# io.net
KiCad netlist of a schematic drawn in Altium Designer
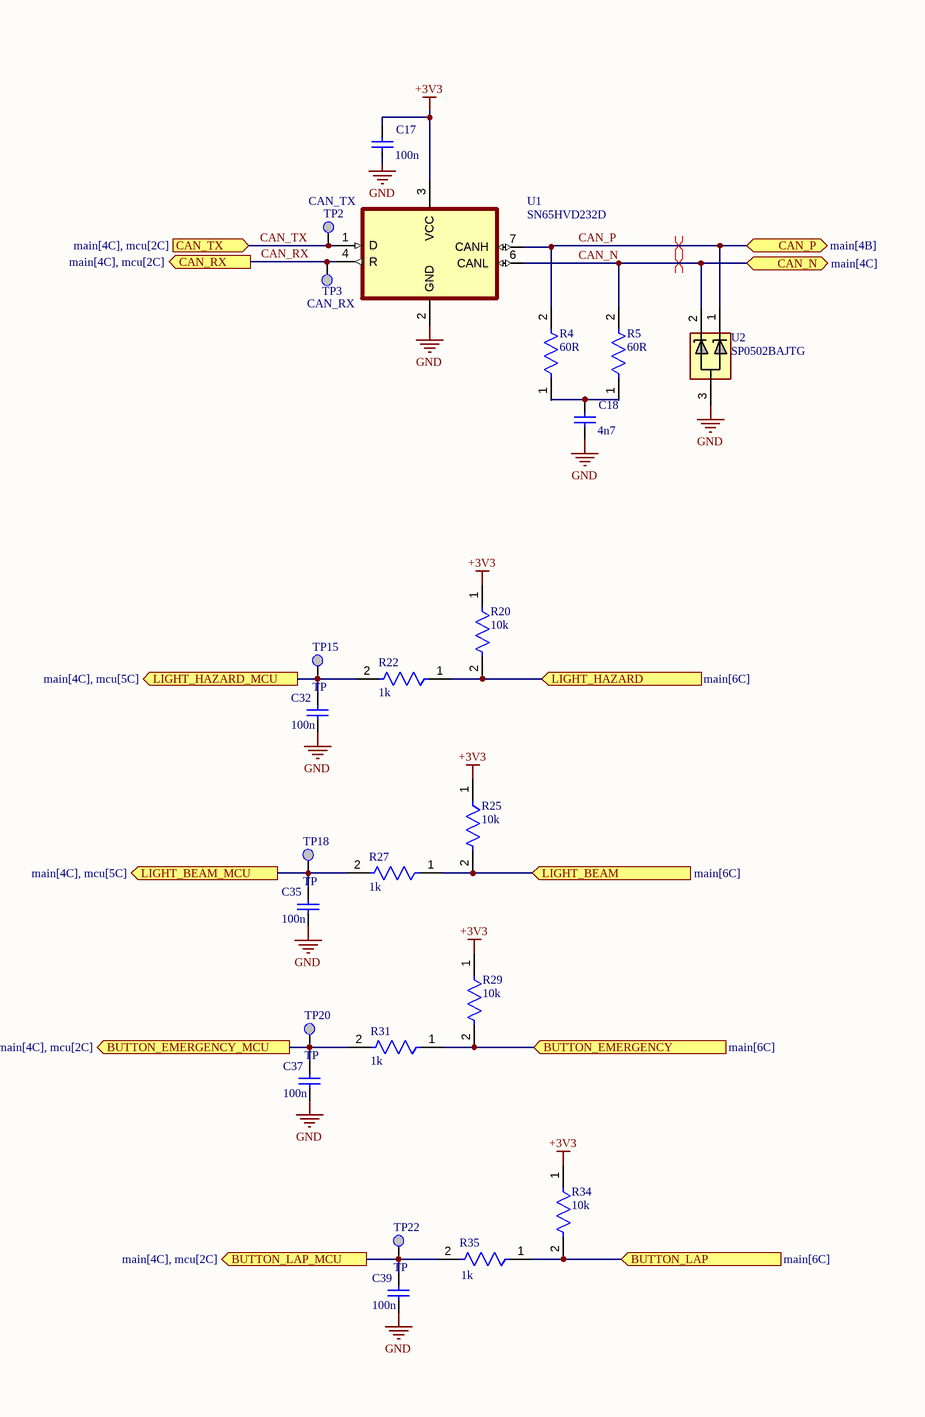
[diagram p0: io.SchDoc, left]
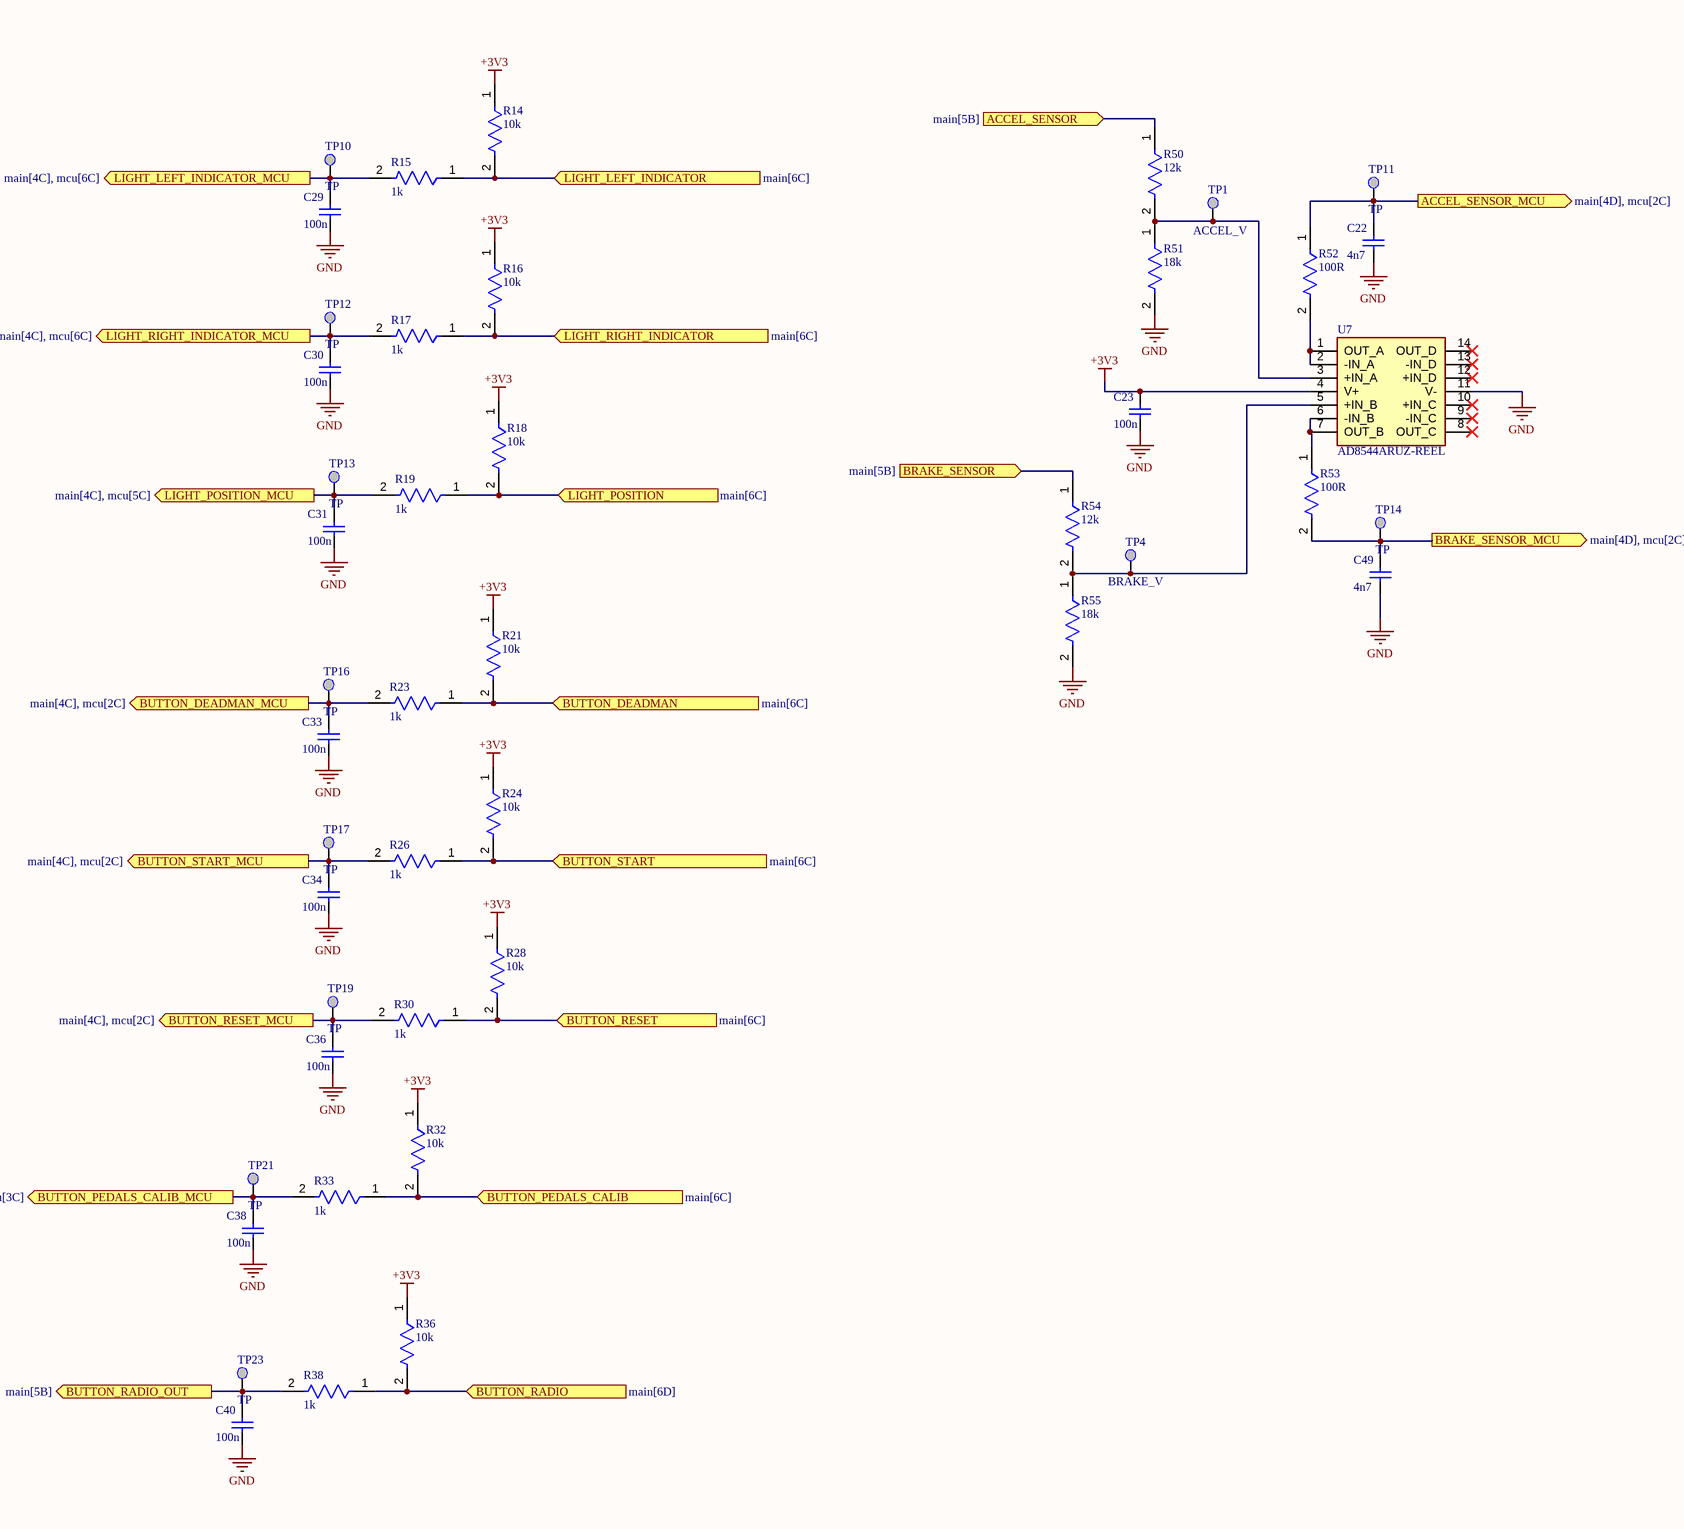
[diagram p1: io.SchDoc, right]

(export (version "E")
  (design (tool "Eeschema 10.0.6"))
  (components
    (comp (ref "C17")
      (value "100n")
      (footprint "CAPC1206(3216)150_L")
      (description "CAP 1.8uF 10V ±5% 1206 (3216 Metric) Thickness 1.45mm SMD")
      (fields (field (name "TOLERANCE") "Â±5%"))
      (libsource (lib "Altium Content Vault") (part "CAP"))
    )
    (comp (ref "C18")
      (value "4n7")
      (footprint "CAPC1206(3216)150_L")
      (description "CAP 1.8uF 10V ±5% 1206 (3216 Metric) Thickness 1.45mm SMD")
      (fields (field (name "TOLERANCE") "Â±5%"))
      (libsource (lib "Altium Content Vault") (part "CAP"))
    )
    (comp (ref "C22")
      (value "4n7")
      (footprint "CAPC1206(3216)150_L")
      (description "CAP 1.8uF 10V ±5% 1206 (3216 Metric) Thickness 1.45mm SMD")
      (fields (field (name "TOLERANCE") "Â±5%"))
      (libsource (lib "Altium Content Vault") (part "CAP"))
    )
    (comp (ref "C23")
      (value "100n")
      (footprint "CAPC1206(3216)150_L")
      (description "CAP 1.8uF 10V ±5% 1206 (3216 Metric) Thickness 1.45mm SMD")
      (fields (field (name "TOLERANCE") "Â±5%"))
      (libsource (lib "Altium Content Vault") (part "CAP"))
    )
    (comp (ref "C29")
      (value "100n")
      (footprint "CAPC1206(3216)150_L")
      (description "CAP 1.8uF 10V ±5% 1206 (3216 Metric) Thickness 1.45mm SMD")
      (fields (field (name "TOLERANCE") "Â±5%"))
      (libsource (lib "Altium Content Vault") (part "CAP"))
    )
    (comp (ref "C30")
      (value "100n")
      (footprint "CAPC1206(3216)150_L")
      (description "CAP 1.8uF 10V ±5% 1206 (3216 Metric) Thickness 1.45mm SMD")
      (fields (field (name "TOLERANCE") "Â±5%"))
      (libsource (lib "Altium Content Vault") (part "CAP"))
    )
    (comp (ref "C31")
      (value "100n")
      (footprint "CAPC1206(3216)150_L")
      (description "CAP 1.8uF 10V ±5% 1206 (3216 Metric) Thickness 1.45mm SMD")
      (fields (field (name "TOLERANCE") "Â±5%"))
      (libsource (lib "Altium Content Vault") (part "CAP"))
    )
    (comp (ref "C32")
      (value "100n")
      (footprint "CAPC1206(3216)150_L")
      (description "CAP 1.8uF 10V ±5% 1206 (3216 Metric) Thickness 1.45mm SMD")
      (fields (field (name "TOLERANCE") "Â±5%"))
      (libsource (lib "Altium Content Vault") (part "CAP"))
    )
    (comp (ref "C33")
      (value "100n")
      (footprint "CAPC1206(3216)150_L")
      (description "CAP 1.8uF 10V ±5% 1206 (3216 Metric) Thickness 1.45mm SMD")
      (fields (field (name "TOLERANCE") "Â±5%"))
      (libsource (lib "Altium Content Vault") (part "CAP"))
    )
    (comp (ref "C34")
      (value "100n")
      (footprint "CAPC1206(3216)150_L")
      (description "CAP 1.8uF 10V ±5% 1206 (3216 Metric) Thickness 1.45mm SMD")
      (fields (field (name "TOLERANCE") "Â±5%"))
      (libsource (lib "Altium Content Vault") (part "CAP"))
    )
    (comp (ref "C35")
      (value "100n")
      (footprint "CAPC1206(3216)150_L")
      (description "CAP 1.8uF 10V ±5% 1206 (3216 Metric) Thickness 1.45mm SMD")
      (fields (field (name "TOLERANCE") "Â±5%"))
      (libsource (lib "Altium Content Vault") (part "CAP"))
    )
    (comp (ref "C36")
      (value "100n")
      (footprint "CAPC1206(3216)150_L")
      (description "CAP 1.8uF 10V ±5% 1206 (3216 Metric) Thickness 1.45mm SMD")
      (fields (field (name "TOLERANCE") "Â±5%"))
      (libsource (lib "Altium Content Vault") (part "CAP"))
    )
    (comp (ref "C37")
      (value "100n")
      (footprint "CAPC1206(3216)150_L")
      (description "CAP 1.8uF 10V ±5% 1206 (3216 Metric) Thickness 1.45mm SMD")
      (fields (field (name "TOLERANCE") "Â±5%"))
      (libsource (lib "Altium Content Vault") (part "CAP"))
    )
    (comp (ref "C38")
      (value "100n")
      (footprint "CAPC1206(3216)150_L")
      (description "CAP 1.8uF 10V ±5% 1206 (3216 Metric) Thickness 1.45mm SMD")
      (fields (field (name "TOLERANCE") "Â±5%"))
      (libsource (lib "Altium Content Vault") (part "CAP"))
    )
    (comp (ref "C39")
      (value "100n")
      (footprint "CAPC1206(3216)150_L")
      (description "CAP 1.8uF 10V ±5% 1206 (3216 Metric) Thickness 1.45mm SMD")
      (fields (field (name "TOLERANCE") "Â±5%"))
      (libsource (lib "Altium Content Vault") (part "CAP"))
    )
    (comp (ref "C40")
      (value "100n")
      (footprint "CAPC1206(3216)150_L")
      (description "CAP 1.8uF 10V ±5% 1206 (3216 Metric) Thickness 1.45mm SMD")
      (fields (field (name "TOLERANCE") "Â±5%"))
      (libsource (lib "Altium Content Vault") (part "CAP"))
    )
    (comp (ref "C49")
      (value "4n7")
      (footprint "CAPC1206(3216)150_L")
      (description "CAP 1.8uF 10V ±5% 1206 (3216 Metric) Thickness 1.45mm SMD")
      (fields (field (name "TOLERANCE") "Â±5%"))
      (libsource (lib "Altium Content Vault") (part "CAP"))
    )
    (comp (ref "R4")
      (value "60R")
      (footprint "FP-RK73H2B-MFG")
      (description "40.2kΩ ±1% 0.25W Chip Resistor 1206 Thick Film AEC-Q200 Qualified")
      (fields (field (name "TOLERANCE") "1%"))
      (libsource (lib "Altium Content Vault") (part "1029c3af85768c4190bb7ad29bc67b5"))
    )
    (comp (ref "R5")
      (value "60R")
      (footprint "FP-RK73H2B-MFG")
      (description "40.2kΩ ±1% 0.25W Chip Resistor 1206 Thick Film AEC-Q200 Qualified")
      (fields (field (name "TOLERANCE") "1%"))
      (libsource (lib "Altium Content Vault") (part "1029c3af85768c4190bb7ad29bc67b5"))
    )
    (comp (ref "R14")
      (value "10k")
      (footprint "FP-RK73H2B-MFG")
      (description "40.2kΩ ±1% 0.25W Chip Resistor 1206 Thick Film AEC-Q200 Qualified")
      (fields (field (name "TOLERANCE") "1%"))
      (libsource (lib "Altium Content Vault") (part "1029c3af85768c4190bb7ad29bc67b5"))
    )
    (comp (ref "R15")
      (value "1k")
      (footprint "FP-RK73H2B-MFG")
      (description "40.2kΩ ±1% 0.25W Chip Resistor 1206 Thick Film AEC-Q200 Qualified")
      (fields (field (name "TOLERANCE") "1%"))
      (libsource (lib "Altium Content Vault") (part "1029c3af85768c4190bb7ad29bc67b5"))
    )
    (comp (ref "R16")
      (value "10k")
      (footprint "FP-RK73H2B-MFG")
      (description "40.2kΩ ±1% 0.25W Chip Resistor 1206 Thick Film AEC-Q200 Qualified")
      (fields (field (name "TOLERANCE") "1%"))
      (libsource (lib "Altium Content Vault") (part "1029c3af85768c4190bb7ad29bc67b5"))
    )
    (comp (ref "R17")
      (value "1k")
      (footprint "FP-RK73H2B-MFG")
      (description "40.2kΩ ±1% 0.25W Chip Resistor 1206 Thick Film AEC-Q200 Qualified")
      (fields (field (name "TOLERANCE") "1%"))
      (libsource (lib "Altium Content Vault") (part "1029c3af85768c4190bb7ad29bc67b5"))
    )
    (comp (ref "R18")
      (value "10k")
      (footprint "FP-RK73H2B-MFG")
      (description "40.2kΩ ±1% 0.25W Chip Resistor 1206 Thick Film AEC-Q200 Qualified")
      (fields (field (name "TOLERANCE") "1%"))
      (libsource (lib "Altium Content Vault") (part "1029c3af85768c4190bb7ad29bc67b5"))
    )
    (comp (ref "R19")
      (value "1k")
      (footprint "FP-RK73H2B-MFG")
      (description "40.2kΩ ±1% 0.25W Chip Resistor 1206 Thick Film AEC-Q200 Qualified")
      (fields (field (name "TOLERANCE") "1%"))
      (libsource (lib "Altium Content Vault") (part "1029c3af85768c4190bb7ad29bc67b5"))
    )
    (comp (ref "R20")
      (value "10k")
      (footprint "FP-RK73H2B-MFG")
      (description "40.2kΩ ±1% 0.25W Chip Resistor 1206 Thick Film AEC-Q200 Qualified")
      (fields (field (name "TOLERANCE") "1%"))
      (libsource (lib "Altium Content Vault") (part "1029c3af85768c4190bb7ad29bc67b5"))
    )
    (comp (ref "R21")
      (value "10k")
      (footprint "FP-RK73H2B-MFG")
      (description "40.2kΩ ±1% 0.25W Chip Resistor 1206 Thick Film AEC-Q200 Qualified")
      (fields (field (name "TOLERANCE") "1%"))
      (libsource (lib "Altium Content Vault") (part "1029c3af85768c4190bb7ad29bc67b5"))
    )
    (comp (ref "R22")
      (value "1k")
      (footprint "FP-RK73H2B-MFG")
      (description "40.2kΩ ±1% 0.25W Chip Resistor 1206 Thick Film AEC-Q200 Qualified")
      (fields (field (name "TOLERANCE") "1%"))
      (libsource (lib "Altium Content Vault") (part "1029c3af85768c4190bb7ad29bc67b5"))
    )
    (comp (ref "R23")
      (value "1k")
      (footprint "FP-RK73H2B-MFG")
      (description "40.2kΩ ±1% 0.25W Chip Resistor 1206 Thick Film AEC-Q200 Qualified")
      (fields (field (name "TOLERANCE") "1%"))
      (libsource (lib "Altium Content Vault") (part "1029c3af85768c4190bb7ad29bc67b5"))
    )
    (comp (ref "R24")
      (value "10k")
      (footprint "FP-RK73H2B-MFG")
      (description "40.2kΩ ±1% 0.25W Chip Resistor 1206 Thick Film AEC-Q200 Qualified")
      (fields (field (name "TOLERANCE") "1%"))
      (libsource (lib "Altium Content Vault") (part "1029c3af85768c4190bb7ad29bc67b5"))
    )
    (comp (ref "R25")
      (value "10k")
      (footprint "FP-RK73H2B-MFG")
      (description "40.2kΩ ±1% 0.25W Chip Resistor 1206 Thick Film AEC-Q200 Qualified")
      (fields (field (name "TOLERANCE") "1%"))
      (libsource (lib "Altium Content Vault") (part "1029c3af85768c4190bb7ad29bc67b5"))
    )
    (comp (ref "R26")
      (value "1k")
      (footprint "FP-RK73H2B-MFG")
      (description "40.2kΩ ±1% 0.25W Chip Resistor 1206 Thick Film AEC-Q200 Qualified")
      (fields (field (name "TOLERANCE") "1%"))
      (libsource (lib "Altium Content Vault") (part "1029c3af85768c4190bb7ad29bc67b5"))
    )
    (comp (ref "R27")
      (value "1k")
      (footprint "FP-RK73H2B-MFG")
      (description "40.2kΩ ±1% 0.25W Chip Resistor 1206 Thick Film AEC-Q200 Qualified")
      (fields (field (name "TOLERANCE") "1%"))
      (libsource (lib "Altium Content Vault") (part "1029c3af85768c4190bb7ad29bc67b5"))
    )
    (comp (ref "R28")
      (value "10k")
      (footprint "FP-RK73H2B-MFG")
      (description "40.2kΩ ±1% 0.25W Chip Resistor 1206 Thick Film AEC-Q200 Qualified")
      (fields (field (name "TOLERANCE") "1%"))
      (libsource (lib "Altium Content Vault") (part "1029c3af85768c4190bb7ad29bc67b5"))
    )
    (comp (ref "R29")
      (value "10k")
      (footprint "FP-RK73H2B-MFG")
      (description "40.2kΩ ±1% 0.25W Chip Resistor 1206 Thick Film AEC-Q200 Qualified")
      (fields (field (name "TOLERANCE") "1%"))
      (libsource (lib "Altium Content Vault") (part "1029c3af85768c4190bb7ad29bc67b5"))
    )
    (comp (ref "R30")
      (value "1k")
      (footprint "FP-RK73H2B-MFG")
      (description "40.2kΩ ±1% 0.25W Chip Resistor 1206 Thick Film AEC-Q200 Qualified")
      (fields (field (name "TOLERANCE") "1%"))
      (libsource (lib "Altium Content Vault") (part "1029c3af85768c4190bb7ad29bc67b5"))
    )
    (comp (ref "R31")
      (value "1k")
      (footprint "FP-RK73H2B-MFG")
      (description "40.2kΩ ±1% 0.25W Chip Resistor 1206 Thick Film AEC-Q200 Qualified")
      (fields (field (name "TOLERANCE") "1%"))
      (libsource (lib "Altium Content Vault") (part "1029c3af85768c4190bb7ad29bc67b5"))
    )
    (comp (ref "R32")
      (value "10k")
      (footprint "FP-RK73H2B-MFG")
      (description "40.2kΩ ±1% 0.25W Chip Resistor 1206 Thick Film AEC-Q200 Qualified")
      (fields (field (name "TOLERANCE") "1%"))
      (libsource (lib "Altium Content Vault") (part "1029c3af85768c4190bb7ad29bc67b5"))
    )
    (comp (ref "R33")
      (value "1k")
      (footprint "FP-RK73H2B-MFG")
      (description "40.2kΩ ±1% 0.25W Chip Resistor 1206 Thick Film AEC-Q200 Qualified")
      (fields (field (name "TOLERANCE") "1%"))
      (libsource (lib "Altium Content Vault") (part "1029c3af85768c4190bb7ad29bc67b5"))
    )
    (comp (ref "R34")
      (value "10k")
      (footprint "FP-RK73H2B-MFG")
      (description "40.2kΩ ±1% 0.25W Chip Resistor 1206 Thick Film AEC-Q200 Qualified")
      (fields (field (name "TOLERANCE") "1%"))
      (libsource (lib "Altium Content Vault") (part "1029c3af85768c4190bb7ad29bc67b5"))
    )
    (comp (ref "R35")
      (value "1k")
      (footprint "FP-RK73H2B-MFG")
      (description "40.2kΩ ±1% 0.25W Chip Resistor 1206 Thick Film AEC-Q200 Qualified")
      (fields (field (name "TOLERANCE") "1%"))
      (libsource (lib "Altium Content Vault") (part "1029c3af85768c4190bb7ad29bc67b5"))
    )
    (comp (ref "R36")
      (value "10k")
      (footprint "FP-RK73H2B-MFG")
      (description "40.2kΩ ±1% 0.25W Chip Resistor 1206 Thick Film AEC-Q200 Qualified")
      (fields (field (name "TOLERANCE") "1%"))
      (libsource (lib "Altium Content Vault") (part "1029c3af85768c4190bb7ad29bc67b5"))
    )
    (comp (ref "R38")
      (value "1k")
      (footprint "FP-RK73H2B-MFG")
      (description "40.2kΩ ±1% 0.25W Chip Resistor 1206 Thick Film AEC-Q200 Qualified")
      (fields (field (name "TOLERANCE") "1%"))
      (libsource (lib "Altium Content Vault") (part "1029c3af85768c4190bb7ad29bc67b5"))
    )
    (comp (ref "R50")
      (value "12k")
      (footprint "FP-RK73H2B-MFG")
      (description "40.2kΩ ±1% 0.25W Chip Resistor 1206 Thick Film AEC-Q200 Qualified")
      (fields (field (name "TOLERANCE") "1%"))
      (libsource (lib "Altium Content Vault") (part "1029c3af85768c4190bb7ad29bc67b5"))
    )
    (comp (ref "R51")
      (value "18k")
      (footprint "FP-RK73H2B-MFG")
      (description "40.2kΩ ±1% 0.25W Chip Resistor 1206 Thick Film AEC-Q200 Qualified")
      (fields (field (name "TOLERANCE") "1%"))
      (libsource (lib "Altium Content Vault") (part "1029c3af85768c4190bb7ad29bc67b5"))
    )
    (comp (ref "R52")
      (value "100R")
      (footprint "FP-RK73H2B-MFG")
      (description "40.2kΩ ±1% 0.25W Chip Resistor 1206 Thick Film AEC-Q200 Qualified")
      (fields (field (name "TOLERANCE") "1%"))
      (libsource (lib "Altium Content Vault") (part "1029c3af85768c4190bb7ad29bc67b5"))
    )
    (comp (ref "R53")
      (value "100R")
      (footprint "FP-RK73H2B-MFG")
      (description "40.2kΩ ±1% 0.25W Chip Resistor 1206 Thick Film AEC-Q200 Qualified")
      (fields (field (name "TOLERANCE") "1%"))
      (libsource (lib "Altium Content Vault") (part "1029c3af85768c4190bb7ad29bc67b5"))
    )
    (comp (ref "R54")
      (value "12k")
      (footprint "FP-RK73H2B-MFG")
      (description "40.2kΩ ±1% 0.25W Chip Resistor 1206 Thick Film AEC-Q200 Qualified")
      (fields (field (name "TOLERANCE") "1%"))
      (libsource (lib "Altium Content Vault") (part "1029c3af85768c4190bb7ad29bc67b5"))
    )
    (comp (ref "R55")
      (value "18k")
      (footprint "FP-RK73H2B-MFG")
      (description "40.2kΩ ±1% 0.25W Chip Resistor 1206 Thick Film AEC-Q200 Qualified")
      (fields (field (name "TOLERANCE") "1%"))
      (libsource (lib "Altium Content Vault") (part "1029c3af85768c4190bb7ad29bc67b5"))
    )
    (comp (ref "TP1")
      (value "ACCEL_V")
      (footprint "Test_Point")
      (libsource (lib "HydrogreenLibrary") (part "TestPoint"))
    )
    (comp (ref "TP2")
      (value "CAN_TX")
      (footprint "Test_Point")
      (libsource (lib "HydrogreenLibrary") (part "TestPoint"))
    )
    (comp (ref "TP3")
      (value "CAN_RX")
      (footprint "Test_Point")
      (libsource (lib "HydrogreenLibrary") (part "TestPoint"))
    )
    (comp (ref "TP4")
      (value "BRAKE_V")
      (footprint "Test_Point")
      (libsource (lib "HydrogreenLibrary") (part "TestPoint"))
    )
    (comp (ref "TP10")
      (value "TP")
      (footprint "Test_Point")
      (libsource (lib "HydrogreenLibrary") (part "TestPoint"))
    )
    (comp (ref "TP11")
      (value "TP")
      (footprint "Test_Point")
      (libsource (lib "HydrogreenLibrary") (part "TestPoint"))
    )
    (comp (ref "TP12")
      (value "TP")
      (footprint "Test_Point")
      (libsource (lib "HydrogreenLibrary") (part "TestPoint"))
    )
    (comp (ref "TP13")
      (value "TP")
      (footprint "Test_Point")
      (libsource (lib "HydrogreenLibrary") (part "TestPoint"))
    )
    (comp (ref "TP14")
      (value "TP")
      (footprint "Test_Point")
      (libsource (lib "HydrogreenLibrary") (part "TestPoint"))
    )
    (comp (ref "TP15")
      (value "TP")
      (footprint "Test_Point")
      (libsource (lib "HydrogreenLibrary") (part "TestPoint"))
    )
    (comp (ref "TP16")
      (value "TP")
      (footprint "Test_Point")
      (libsource (lib "HydrogreenLibrary") (part "TestPoint"))
    )
    (comp (ref "TP17")
      (value "TP")
      (footprint "Test_Point")
      (libsource (lib "HydrogreenLibrary") (part "TestPoint"))
    )
    (comp (ref "TP18")
      (value "TP")
      (footprint "Test_Point")
      (libsource (lib "HydrogreenLibrary") (part "TestPoint"))
    )
    (comp (ref "TP19")
      (value "TP")
      (footprint "Test_Point")
      (libsource (lib "HydrogreenLibrary") (part "TestPoint"))
    )
    (comp (ref "TP20")
      (value "TP")
      (footprint "Test_Point")
      (libsource (lib "HydrogreenLibrary") (part "TestPoint"))
    )
    (comp (ref "TP21")
      (value "TP")
      (footprint "Test_Point")
      (libsource (lib "HydrogreenLibrary") (part "TestPoint"))
    )
    (comp (ref "TP22")
      (value "TP")
      (footprint "Test_Point")
      (libsource (lib "HydrogreenLibrary") (part "TestPoint"))
    )
    (comp (ref "TP23")
      (value "TP")
      (footprint "Test_Point")
      (libsource (lib "HydrogreenLibrary") (part "TestPoint"))
    )
    (comp (ref "U1")
      (value "SN65HVD232D")
      (footprint "SN65HVD232D")
      (description "Texas Instruments - SN65HVD232DR - Can Transceiver, 1MBPS, 1/1, 3.3V, SOIC-8, Full Reel")
      (fields
        (field (name "MF") "Texas Instruments")
        (field (name "MANUFACTURER PART NUMBER") "SN65HVD232DR")
      )
      (libsource (lib "HydrogreenLibrary") (part "SN65HVD232D"))
    )
    (comp (ref "U2")
      (value "SP0502BAJTG")
      (footprint "SOT132P220X110-3N")
      (description "Integrated Circuit")
      (fields (field (name "MOUSER PART NUMBER") "576-SP0502BAJTG"))
      (libsource (lib "HydrogreenLibrary") (part "SP0502BAJTG"))
    )
    (comp (ref "U7")
      (value "AD8544ARUZ-REEL")
      (footprint "AD8544ARUZ-REEL")
      (fields (field (name "MOUSER PART NUMBER") "584-AD8544ARUZ-R"))
      (libsource (lib "HydrogreenLibrary") (part "AD8544ARUZ-REEL"))
    )
  )
  (nets
    (net (code "1") (name "+3V3") (class "Default")
      (node (ref "C17") (pin "1") (pinfunction "1_1") (pintype "passive"))
      (node (ref "C23") (pin "1") (pinfunction "1_1") (pintype "passive"))
      (node (ref "R14") (pin "1") (pinfunction "1_1") (pintype "passive"))
      (node (ref "R16") (pin "1") (pinfunction "1_1") (pintype "passive"))
      (node (ref "R18") (pin "1") (pinfunction "1_1") (pintype "passive"))
      (node (ref "R20") (pin "1") (pinfunction "1_1") (pintype "passive"))
      (node (ref "R21") (pin "1") (pinfunction "1_1") (pintype "passive"))
      (node (ref "R24") (pin "1") (pinfunction "1_1") (pintype "passive"))
      (node (ref "R25") (pin "1") (pinfunction "1_1") (pintype "passive"))
      (node (ref "R28") (pin "1") (pinfunction "1_1") (pintype "passive"))
      (node (ref "R29") (pin "1") (pinfunction "1_1") (pintype "passive"))
      (node (ref "R32") (pin "1") (pinfunction "1_1") (pintype "passive"))
      (node (ref "R34") (pin "1") (pinfunction "1_1") (pintype "passive"))
      (node (ref "R36") (pin "1") (pinfunction "1_1") (pintype "passive"))
      (node (ref "U1") (pin "3") (pinfunction "VCC_3") (pintype "power_in"))
      (node (ref "U7") (pin "4") (pinfunction "V+_4") (pintype "passive"))
    )
    (net (code "2") (name "/ACCEL_SENSOR") (class "Default")
      (node (ref "R50") (pin "1") (pinfunction "1_1") (pintype "passive"))
    )
    (net (code "3") (name "/ACCEL_SENSOR_MCU") (class "Default")
      (node (ref "C22") (pin "1") (pinfunction "1_1") (pintype "passive"))
      (node (ref "R52") (pin "1") (pinfunction "1_1") (pintype "passive"))
      (node (ref "TP11") (pin "1") (pinfunction "1_1") (pintype "passive"))
    )
    (net (code "4") (name "/BRAKE_SENSOR") (class "Default")
      (node (ref "R54") (pin "1") (pinfunction "1_1") (pintype "passive"))
    )
    (net (code "5") (name "/BRAKE_SENSOR_MCU") (class "Default")
      (node (ref "C49") (pin "1") (pinfunction "1_1") (pintype "passive"))
      (node (ref "R53") (pin "2") (pinfunction "2_2") (pintype "passive"))
      (node (ref "TP14") (pin "1") (pinfunction "1_1") (pintype "passive"))
    )
    (net (code "6") (name "/BUTTON_DEADMAN") (class "Default")
      (node (ref "R21") (pin "2") (pinfunction "2_2") (pintype "passive"))
      (node (ref "R23") (pin "1") (pinfunction "1_1") (pintype "passive"))
    )
    (net (code "7") (name "/BUTTON_DEADMAN_MCU") (class "Default")
      (node (ref "C33") (pin "1") (pinfunction "1_1") (pintype "passive"))
      (node (ref "R23") (pin "2") (pinfunction "2_2") (pintype "passive"))
      (node (ref "TP16") (pin "1") (pinfunction "1_1") (pintype "passive"))
    )
    (net (code "8") (name "/BUTTON_EMERGENCY") (class "Default")
      (node (ref "R29") (pin "2") (pinfunction "2_2") (pintype "passive"))
      (node (ref "R31") (pin "1") (pinfunction "1_1") (pintype "passive"))
    )
    (net (code "9") (name "/BUTTON_EMERGENCY_MCU") (class "Default")
      (node (ref "C37") (pin "1") (pinfunction "1_1") (pintype "passive"))
      (node (ref "R31") (pin "2") (pinfunction "2_2") (pintype "passive"))
      (node (ref "TP20") (pin "1") (pinfunction "1_1") (pintype "passive"))
    )
    (net (code "10") (name "/BUTTON_LAP") (class "Default")
      (node (ref "R34") (pin "2") (pinfunction "2_2") (pintype "passive"))
      (node (ref "R35") (pin "1") (pinfunction "1_1") (pintype "passive"))
    )
    (net (code "11") (name "/BUTTON_LAP_MCU") (class "Default")
      (node (ref "C39") (pin "1") (pinfunction "1_1") (pintype "passive"))
      (node (ref "R35") (pin "2") (pinfunction "2_2") (pintype "passive"))
      (node (ref "TP22") (pin "1") (pinfunction "1_1") (pintype "passive"))
    )
    (net (code "12") (name "/BUTTON_PEDALS_CALIB") (class "Default")
      (node (ref "R32") (pin "2") (pinfunction "2_2") (pintype "passive"))
      (node (ref "R33") (pin "1") (pinfunction "1_1") (pintype "passive"))
    )
    (net (code "13") (name "/BUTTON_PEDALS_CALIB_MCU") (class "Default")
      (node (ref "C38") (pin "1") (pinfunction "1_1") (pintype "passive"))
      (node (ref "R33") (pin "2") (pinfunction "2_2") (pintype "passive"))
      (node (ref "TP21") (pin "1") (pinfunction "1_1") (pintype "passive"))
    )
    (net (code "14") (name "/BUTTON_RADIO") (class "Default")
      (node (ref "R36") (pin "2") (pinfunction "2_2") (pintype "passive"))
      (node (ref "R38") (pin "1") (pinfunction "1_1") (pintype "passive"))
    )
    (net (code "15") (name "/BUTTON_RADIO_OUT") (class "Default")
      (node (ref "C40") (pin "1") (pinfunction "1_1") (pintype "passive"))
      (node (ref "R38") (pin "2") (pinfunction "2_2") (pintype "passive"))
      (node (ref "TP23") (pin "1") (pinfunction "1_1") (pintype "passive"))
    )
    (net (code "16") (name "/BUTTON_RESET") (class "Default")
      (node (ref "R28") (pin "2") (pinfunction "2_2") (pintype "passive"))
      (node (ref "R30") (pin "1") (pinfunction "1_1") (pintype "passive"))
    )
    (net (code "17") (name "/BUTTON_RESET_MCU") (class "Default")
      (node (ref "C36") (pin "1") (pinfunction "1_1") (pintype "passive"))
      (node (ref "R30") (pin "2") (pinfunction "2_2") (pintype "passive"))
      (node (ref "TP19") (pin "1") (pinfunction "1_1") (pintype "passive"))
    )
    (net (code "18") (name "/BUTTON_START") (class "Default")
      (node (ref "R24") (pin "2") (pinfunction "2_2") (pintype "passive"))
      (node (ref "R26") (pin "1") (pinfunction "1_1") (pintype "passive"))
    )
    (net (code "19") (name "/BUTTON_START_MCU") (class "Default")
      (node (ref "C34") (pin "1") (pinfunction "1_1") (pintype "passive"))
      (node (ref "R26") (pin "2") (pinfunction "2_2") (pintype "passive"))
      (node (ref "TP17") (pin "1") (pinfunction "1_1") (pintype "passive"))
    )
    (net (code "20") (name "/CAN_N") (class "Default")
      (node (ref "R5") (pin "2") (pinfunction "2_2") (pintype "passive"))
      (node (ref "U1") (pin "6") (pinfunction "CANL_6") (pintype "bidirectional"))
      (node (ref "U2") (pin "2") (pintype "passive"))
    )
    (net (code "21") (name "/CAN_P") (class "Default")
      (node (ref "R4") (pin "2") (pinfunction "2_2") (pintype "passive"))
      (node (ref "U1") (pin "7") (pinfunction "CANH_7") (pintype "bidirectional"))
      (node (ref "U2") (pin "1") (pintype "passive"))
    )
    (net (code "22") (name "/CAN_RX") (class "Default")
      (node (ref "TP3") (pin "1") (pinfunction "1_1") (pintype "passive"))
      (node (ref "U1") (pin "4") (pinfunction "R_4") (pintype "output"))
    )
    (net (code "23") (name "/CAN_TX") (class "Default")
      (node (ref "TP2") (pin "1") (pinfunction "1_1") (pintype "passive"))
      (node (ref "U1") (pin "1") (pinfunction "D_1") (pintype "input"))
    )
    (net (code "24") (name "/LIGHT_BEAM") (class "Default")
      (node (ref "R25") (pin "2") (pinfunction "2_2") (pintype "passive"))
      (node (ref "R27") (pin "1") (pinfunction "1_1") (pintype "passive"))
    )
    (net (code "25") (name "/LIGHT_BEAM_MCU") (class "Default")
      (node (ref "C35") (pin "1") (pinfunction "1_1") (pintype "passive"))
      (node (ref "R27") (pin "2") (pinfunction "2_2") (pintype "passive"))
      (node (ref "TP18") (pin "1") (pinfunction "1_1") (pintype "passive"))
    )
    (net (code "26") (name "/LIGHT_HAZARD") (class "Default")
      (node (ref "R20") (pin "2") (pinfunction "2_2") (pintype "passive"))
      (node (ref "R22") (pin "1") (pinfunction "1_1") (pintype "passive"))
    )
    (net (code "27") (name "/LIGHT_HAZARD_MCU") (class "Default")
      (node (ref "C32") (pin "1") (pinfunction "1_1") (pintype "passive"))
      (node (ref "R22") (pin "2") (pinfunction "2_2") (pintype "passive"))
      (node (ref "TP15") (pin "1") (pinfunction "1_1") (pintype "passive"))
    )
    (net (code "28") (name "/LIGHT_LEFT_INDICATOR") (class "Default")
      (node (ref "R14") (pin "2") (pinfunction "2_2") (pintype "passive"))
      (node (ref "R15") (pin "1") (pinfunction "1_1") (pintype "passive"))
    )
    (net (code "29") (name "/LIGHT_LEFT_INDICATOR_MCU") (class "Default")
      (node (ref "C29") (pin "1") (pinfunction "1_1") (pintype "passive"))
      (node (ref "R15") (pin "2") (pinfunction "2_2") (pintype "passive"))
      (node (ref "TP10") (pin "1") (pinfunction "1_1") (pintype "passive"))
    )
    (net (code "30") (name "/LIGHT_POSITION") (class "Default")
      (node (ref "R18") (pin "2") (pinfunction "2_2") (pintype "passive"))
      (node (ref "R19") (pin "1") (pinfunction "1_1") (pintype "passive"))
    )
    (net (code "31") (name "/LIGHT_POSITION_MCU") (class "Default")
      (node (ref "C31") (pin "1") (pinfunction "1_1") (pintype "passive"))
      (node (ref "R19") (pin "2") (pinfunction "2_2") (pintype "passive"))
      (node (ref "TP13") (pin "1") (pinfunction "1_1") (pintype "passive"))
    )
    (net (code "32") (name "/LIGHT_RIGHT_INDICATOR") (class "Default")
      (node (ref "R16") (pin "2") (pinfunction "2_2") (pintype "passive"))
      (node (ref "R17") (pin "1") (pinfunction "1_1") (pintype "passive"))
    )
    (net (code "33") (name "/LIGHT_RIGHT_INDICATOR_MCU") (class "Default")
      (node (ref "C30") (pin "1") (pinfunction "1_1") (pintype "passive"))
      (node (ref "R17") (pin "2") (pinfunction "2_2") (pintype "passive"))
      (node (ref "TP12") (pin "1") (pinfunction "1_1") (pintype "passive"))
    )
    (net (code "34") (name "GND") (class "Default")
      (node (ref "C17") (pin "2") (pinfunction "2_2") (pintype "passive"))
      (node (ref "C18") (pin "2") (pinfunction "2_2") (pintype "passive"))
      (node (ref "C22") (pin "2") (pinfunction "2_2") (pintype "passive"))
      (node (ref "C23") (pin "2") (pinfunction "2_2") (pintype "passive"))
      (node (ref "C29") (pin "2") (pinfunction "2_2") (pintype "passive"))
      (node (ref "C30") (pin "2") (pinfunction "2_2") (pintype "passive"))
      (node (ref "C31") (pin "2") (pinfunction "2_2") (pintype "passive"))
      (node (ref "C32") (pin "2") (pinfunction "2_2") (pintype "passive"))
      (node (ref "C33") (pin "2") (pinfunction "2_2") (pintype "passive"))
      (node (ref "C34") (pin "2") (pinfunction "2_2") (pintype "passive"))
      (node (ref "C35") (pin "2") (pinfunction "2_2") (pintype "passive"))
      (node (ref "C36") (pin "2") (pinfunction "2_2") (pintype "passive"))
      (node (ref "C37") (pin "2") (pinfunction "2_2") (pintype "passive"))
      (node (ref "C38") (pin "2") (pinfunction "2_2") (pintype "passive"))
      (node (ref "C39") (pin "2") (pinfunction "2_2") (pintype "passive"))
      (node (ref "C40") (pin "2") (pinfunction "2_2") (pintype "passive"))
      (node (ref "C49") (pin "2") (pinfunction "2_2") (pintype "passive"))
      (node (ref "R51") (pin "2") (pinfunction "2_2") (pintype "passive"))
      (node (ref "R55") (pin "2") (pinfunction "2_2") (pintype "passive"))
      (node (ref "U1") (pin "2") (pinfunction "GND_2") (pintype "power_in"))
      (node (ref "U2") (pin "3") (pintype "passive"))
      (node (ref "U7") (pin "11") (pinfunction "V-_11") (pintype "passive"))
    )
    (net (code "35") (name "Net-(C18-Pad1)") (class "Default")
      (node (ref "C18") (pin "1") (pinfunction "1_1") (pintype "passive"))
      (node (ref "R4") (pin "1") (pinfunction "1_1") (pintype "passive"))
      (node (ref "R5") (pin "1") (pinfunction "1_1") (pintype "passive"))
    )
    (net (code "36") (name "Net-(U7-+IN_A)") (class "Default")
      (node (ref "R50") (pin "2") (pinfunction "2_2") (pintype "passive"))
      (node (ref "R51") (pin "1") (pinfunction "1_1") (pintype "passive"))
      (node (ref "TP1") (pin "1") (pinfunction "1_1") (pintype "passive"))
      (node (ref "U7") (pin "3") (pinfunction "+IN_A_3") (pintype "passive"))
    )
    (net (code "37") (name "Net-(U7-+IN_B)") (class "Default")
      (node (ref "R54") (pin "2") (pinfunction "2_2") (pintype "passive"))
      (node (ref "R55") (pin "1") (pinfunction "1_1") (pintype "passive"))
      (node (ref "TP4") (pin "1") (pinfunction "1_1") (pintype "passive"))
      (node (ref "U7") (pin "5") (pinfunction "+IN_B_5") (pintype "passive"))
    )
    (net (code "38") (name "Net-(U7--IN_A)") (class "Default")
      (node (ref "R52") (pin "2") (pinfunction "2_2") (pintype "passive"))
      (node (ref "U7") (pin "1") (pinfunction "OUT_A_1") (pintype "passive"))
      (node (ref "U7") (pin "2") (pinfunction "-IN_A_2") (pintype "passive"))
    )
    (net (code "39") (name "Net-(U7--IN_B)") (class "Default")
      (node (ref "R53") (pin "1") (pinfunction "1_1") (pintype "passive"))
      (node (ref "U7") (pin "6") (pinfunction "-IN_B_6") (pintype "passive"))
      (node (ref "U7") (pin "7") (pinfunction "OUT_B_7") (pintype "passive"))
    )
    (net (code "40") (name "unconnected-(U7-+IN_C-Pad10)") (class "Default")
      (node (ref "U7") (pin "10") (pinfunction "+IN_C_10") (pintype "passive+no_connect"))
    )
    (net (code "41") (name "unconnected-(U7-+IN_D-Pad12)") (class "Default")
      (node (ref "U7") (pin "12") (pinfunction "+IN_D_12") (pintype "passive+no_connect"))
    )
    (net (code "42") (name "unconnected-(U7--IN_C-Pad9)") (class "Default")
      (node (ref "U7") (pin "9") (pinfunction "-IN_C_9") (pintype "passive+no_connect"))
    )
    (net (code "43") (name "unconnected-(U7--IN_D-Pad13)") (class "Default")
      (node (ref "U7") (pin "13") (pinfunction "-IN_D_13") (pintype "passive+no_connect"))
    )
    (net (code "44") (name "unconnected-(U7-OUT_C-Pad8)") (class "Default")
      (node (ref "U7") (pin "8") (pinfunction "OUT_C_8") (pintype "passive+no_connect"))
    )
    (net (code "45") (name "unconnected-(U7-OUT_D-Pad14)") (class "Default")
      (node (ref "U7") (pin "14") (pinfunction "OUT_D_14") (pintype "passive+no_connect"))
    )
  )
)
